# wd-switch.net
KiCad netlist of a schematic drawn in EAGLE
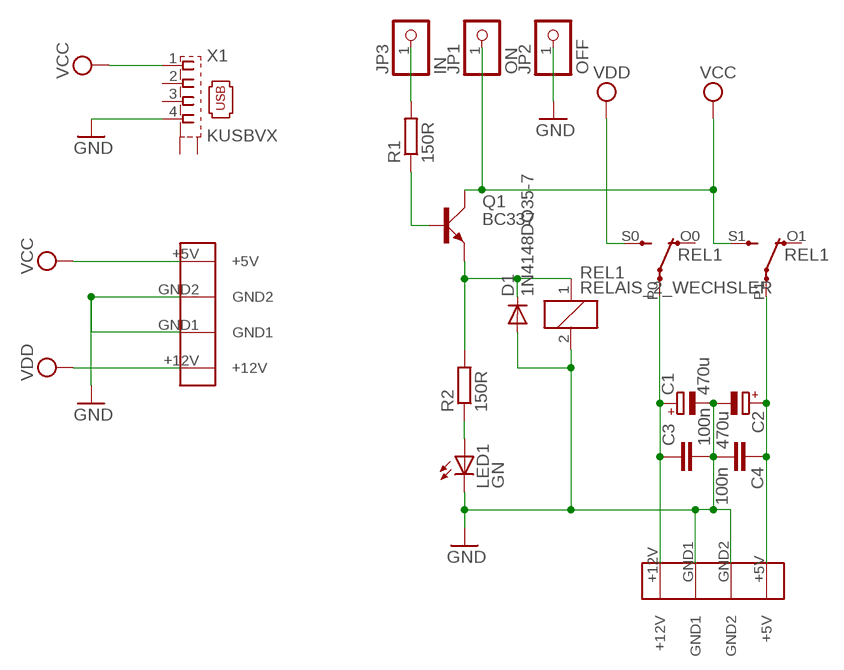
[diagram p0: schematic, sheet 1]

(export (version "E")
  (design (tool "Eeschema 10.0.6"))
  (components
    (comp (ref "C1")
      (value "470u")
      (footprint "eagle-import:E3,5-8")
      (libsource (lib "eagle-import") (part "CPOL-EUE3.5-8"))
    )
    (comp (ref "C2")
      (value "470u")
      (footprint "eagle-import:E3,5-8")
      (libsource (lib "eagle-import") (part "CPOL-EUE3.5-8"))
    )
    (comp (ref "C3")
      (value "100n")
      (footprint "eagle-import:C025-024X044")
      (libsource (lib "eagle-import") (part "C-EU025-024X044"))
    )
    (comp (ref "C4")
      (value "100n")
      (footprint "eagle-import:C025-024X044")
      (libsource (lib "eagle-import") (part "C-EU025-024X044"))
    )
    (comp (ref "D1")
      (value "1N4148DO35-7")
      (footprint "eagle-import:DO35-7")
      (libsource (lib "eagle-import") (part "1N4148DO35-7"))
    )
    (comp (ref "IN")
      (value "PSW_5")
      (footprint "eagle-import:PSW_5")
      (libsource (lib "eagle-import") (part "PSW_5"))
    )
    (comp (ref "JP1")
      (value "ON")
      (footprint "eagle-import:1X01")
      (libsource (lib "eagle-import") (part "PINHD-1X1"))
    )
    (comp (ref "JP2")
      (value "OFF")
      (footprint "eagle-import:1X01")
      (libsource (lib "eagle-import") (part "PINHD-1X1"))
    )
    (comp (ref "JP3")
      (value "IN")
      (footprint "eagle-import:1X01")
      (libsource (lib "eagle-import") (part "PINHD-1X1"))
    )
    (comp (ref "LED1")
      (value "GN")
      (footprint "eagle-import:LED5MM")
      (libsource (lib "eagle-import") (part "LED5MM"))
    )
    (comp (ref "OUT")
      (value "PSW_5")
      (footprint "eagle-import:PSW_5")
      (libsource (lib "eagle-import") (part "PSW_5"))
    )
    (comp (ref "Q1")
      (value "BC337")
      (footprint "eagle-import:SOT54A")
      (libsource (lib "eagle-import") (part "BC337"))
    )
    (comp (ref "R1")
      (value "150R")
      (footprint "eagle-import:0207_2V")
      (libsource (lib "eagle-import") (part "R-EU_0207/2V"))
    )
    (comp (ref "R2")
      (value "150R")
      (footprint "eagle-import:0207_7")
      (libsource (lib "eagle-import") (part "R-EU_0207/7"))
    )
    (comp (ref "REL1")
      (value "RELAIS_2_WECHSLER")
      (footprint "eagle-import:RELAIS_DIL_M4")
      (libsource (lib "eagle-import") (part "RELAIS_2_WECHSLER"))
    )
    (comp (ref "X1")
      (value "KUSBVX")
      (footprint "eagle-import:KUSBVX")
      (libsource (lib "eagle-import") (part "KUSBVX"))
    )
  )
  (nets
    (net (code "1") (name "GND") (class "Default")
      (node (ref "C1") (pin "-") (pinfunction "-_-") (pintype "passive"))
      (node (ref "C2") (pin "-") (pinfunction "-_-") (pintype "passive"))
      (node (ref "C3") (pin "2") (pinfunction "2_2") (pintype "passive"))
      (node (ref "C4") (pin "2") (pinfunction "2_2") (pintype "passive"))
      (node (ref "D1") (pin "A") (pinfunction "A_A") (pintype "passive"))
      (node (ref "IN") (pin "GND1") (pinfunction "GND1_GND1") (pintype "bidirectional"))
      (node (ref "IN") (pin "GND2") (pinfunction "GND2_GND2") (pintype "bidirectional"))
      (node (ref "JP2") (pin "1") (pinfunction "1_1") (pintype "passive"))
      (node (ref "LED1") (pin "K") (pinfunction "C_K") (pintype "passive"))
      (node (ref "OUT") (pin "GND1") (pinfunction "GND1_GND1") (pintype "bidirectional"))
      (node (ref "OUT") (pin "GND2") (pinfunction "GND2_GND2") (pintype "bidirectional"))
      (node (ref "REL1") (pin "2") (pinfunction "2_2") (pintype "passive"))
      (node (ref "X1") (pin "4") (pinfunction "4_4") (pintype "passive"))
    )
    (net (code "2") (name "Net-(D1-PadC)") (class "Default")
      (node (ref "D1") (pin "C") (pinfunction "C_C") (pintype "passive"))
      (node (ref "Q1") (pin "E") (pinfunction "E_E") (pintype "passive"))
      (node (ref "R2") (pin "2") (pinfunction "2_2") (pintype "passive"))
      (node (ref "REL1") (pin "1") (pinfunction "1_1") (pintype "passive"))
    )
    (net (code "3") (name "Net-(JP3-Pad1)") (class "Default")
      (node (ref "JP3") (pin "1") (pinfunction "1_1") (pintype "passive"))
      (node (ref "R1") (pin "2") (pinfunction "2_2") (pintype "passive"))
    )
    (net (code "4") (name "Net-(LED1-PadA)") (class "Default")
      (node (ref "LED1") (pin "A") (pinfunction "A_A") (pintype "passive"))
      (node (ref "R2") (pin "1") (pinfunction "1_1") (pintype "passive"))
    )
    (net (code "5") (name "Net-(Q1-PadB)") (class "Default")
      (node (ref "Q1") (pin "B") (pinfunction "B_B") (pintype "passive"))
      (node (ref "R1") (pin "1") (pinfunction "1_1") (pintype "passive"))
    )
    (net (code "6") (name "Net-(REL1B-P)") (class "Default")
      (node (ref "C1") (pin "+") (pinfunction "+_+") (pintype "passive"))
      (node (ref "C3") (pin "1") (pinfunction "1_1") (pintype "passive"))
      (node (ref "OUT") (pin "+12V") (pinfunction "+12V_+12V") (pintype "bidirectional"))
      (node (ref "REL1") (pin "P0") (pinfunction "P_P0") (pintype "passive"))
    )
    (net (code "7") (name "Net-(REL1C-P)") (class "Default")
      (node (ref "C2") (pin "+") (pinfunction "+_+") (pintype "passive"))
      (node (ref "C4") (pin "1") (pinfunction "1_1") (pintype "passive"))
      (node (ref "OUT") (pin "+5V") (pinfunction "+5V_+5V") (pintype "bidirectional"))
      (node (ref "REL1") (pin "P1") (pinfunction "P_P1") (pintype "passive"))
    )
    (net (code "8") (name "VCC") (class "Default")
      (node (ref "IN") (pin "+5V") (pinfunction "+5V_+5V") (pintype "bidirectional"))
      (node (ref "JP1") (pin "1") (pinfunction "1_1") (pintype "passive"))
      (node (ref "Q1") (pin "C") (pinfunction "C_C") (pintype "passive"))
      (node (ref "REL1") (pin "S1") (pinfunction "S_S1") (pintype "passive"))
      (node (ref "X1") (pin "1") (pinfunction "1_1") (pintype "passive"))
    )
    (net (code "9") (name "VDD") (class "Default")
      (node (ref "IN") (pin "+12V") (pinfunction "+12V_+12V") (pintype "bidirectional"))
      (node (ref "REL1") (pin "S0") (pinfunction "S_S0") (pintype "passive"))
    )
    (net (code "10") (name "unconnected-(REL1B-O-PadO0)") (class "Default")
      (node (ref "REL1") (pin "O0") (pinfunction "O_O0") (pintype "passive"))
    )
    (net (code "11") (name "unconnected-(REL1C-O-PadO1)") (class "Default")
      (node (ref "REL1") (pin "O1") (pinfunction "O_O1") (pintype "passive"))
    )
    (net (code "12") (name "unconnected-(X1-Pad2)") (class "Default")
      (node (ref "X1") (pin "2") (pinfunction "2_2") (pintype "passive"))
    )
    (net (code "13") (name "unconnected-(X1-Pad3)") (class "Default")
      (node (ref "X1") (pin "3") (pinfunction "3_3") (pintype "passive"))
    )
    (net (code "14") (name "unconnected-(X1-S1-PadM1)") (class "Default")
      (node (ref "X1") (pin "M1") (pinfunction "S1_M1") (pintype "passive"))
    )
    (net (code "15") (name "unconnected-(X1-S2-PadM2)") (class "Default")
      (node (ref "X1") (pin "M2") (pinfunction "S2_M2") (pintype "passive"))
    )
  )
)
